# USB_9.net
KiCad netlist of a schematic drawn in Altium Designer
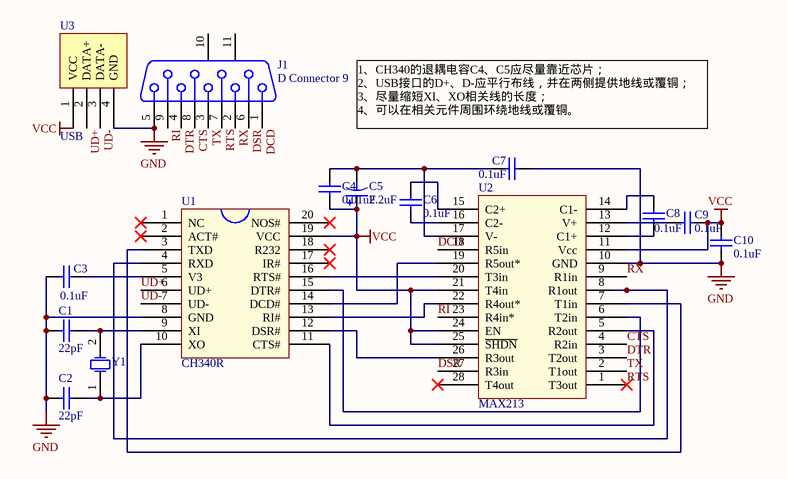
[diagram p0: USB转9线串口.SchDoc]

(export (version "E")
  (design (tool "Eeschema 10.0.6"))
  (components
    (comp (ref "C1")
      (value "22pF")
      (footprint "C1206")
      (description "Capacitor")
      (fields (field (name "PUBLISHER") "Altium Limited"))
      (libsource (lib "Miscellaneous Devices") (part "Cap"))
    )
    (comp (ref "C2")
      (value "22pF")
      (footprint "C1206")
      (description "Capacitor")
      (fields (field (name "PUBLISHER") "Altium Limited"))
      (libsource (lib "Miscellaneous Devices") (part "Cap"))
    )
    (comp (ref "C3")
      (value "0.1uF")
      (footprint "C1206")
      (description "Capacitor")
      (fields (field (name "PUBLISHER") "Altium Limited"))
      (libsource (lib "Miscellaneous Devices") (part "Cap"))
    )
    (comp (ref "C4")
      (value "0.01uF")
      (footprint "C1206")
      (description "Capacitor")
      (fields (field (name "PUBLISHER") "Altium Limited"))
      (libsource (lib "Miscellaneous Devices") (part "Cap"))
    )
    (comp (ref "C5")
      (value "2.2uF")
      (footprint "C1206")
      (description "Polarized Capacitor (Radial)")
      (fields (field (name "Comment") "Cap Pol1") (field (name "PUBLISHER") "Altium Limited"))
      (libsource (lib "Miscellaneous Devices") (part "Cap Pol1"))
    )
    (comp (ref "C6")
      (value "0.1uF")
      (footprint "C1206")
      (description "Capacitor")
      (fields (field (name "PUBLISHER") "Altium Limited"))
      (libsource (lib "Miscellaneous Devices") (part "Cap"))
    )
    (comp (ref "C7")
      (value "0.1uF")
      (footprint "C1206")
      (description "Capacitor")
      (fields (field (name "PUBLISHER") "Altium Limited"))
      (libsource (lib "Miscellaneous Devices") (part "Cap"))
    )
    (comp (ref "C8")
      (value "0.1uF")
      (footprint "C1206")
      (description "Capacitor")
      (fields (field (name "PUBLISHER") "Altium Limited"))
      (libsource (lib "Miscellaneous Devices") (part "Cap"))
    )
    (comp (ref "C9")
      (value "0.1uF")
      (footprint "C1206")
      (description "Capacitor")
      (fields (field (name "PUBLISHER") "Altium Limited"))
      (libsource (lib "Miscellaneous Devices") (part "Cap"))
    )
    (comp (ref "C10")
      (value "0.1uF")
      (footprint "C1206")
      (description "Capacitor")
      (fields (field (name "PUBLISHER") "Altium Limited"))
      (libsource (lib "Miscellaneous Devices") (part "Cap"))
    )
    (comp (ref "J1")
      (value "D Connector 9")
      (footprint "DSUB1.385-2H9")
      (description "Receptacle Assembly, 9 Position, Right Angle")
      (fields (field (name "PUBLISHER") "Altium Limited"))
      (libsource (lib "自定义库") (part "D Connector 9"))
    )
    (comp (ref "U1") (value "CH340R") (footprint "SSOP-20") (libsource (lib "自定义库") (part "CH340R")))
    (comp (ref "U2") (value "MAX213") (footprint "SSOP-28") (libsource (lib "自定义库") (part "MAX213")))
    (comp (ref "U3") (value "USB") (footprint "USB-A") (libsource (lib "自定义库") (part "USB")))
    (comp (ref "Y1")
      (value "XTAL")
      (footprint "R38")
      (description "Crystal Oscillator")
      (fields (field (name "PUBLISHER") "Altium Limited"))
      (libsource (lib "自定义库") (part "XTAL"))
    )
  )
  (nets
    (net (code "1") (name "/CTS") (class "Default")
      (node (ref "J1") (pin "8") (pinfunction "8_8") (pintype "passive"))
      (node (ref "U2") (pin "4") (pinfunction "R2in_4") (pintype "passive"))
    )
    (net (code "2") (name "/DCD") (class "Default")
      (node (ref "J1") (pin "1") (pinfunction "1_1") (pintype "passive"))
      (node (ref "U2") (pin "18") (pinfunction "R5in_18") (pintype "passive"))
    )
    (net (code "3") (name "/DSR") (class "Default")
      (node (ref "J1") (pin "6") (pinfunction "6_6") (pintype "passive"))
      (node (ref "U2") (pin "27") (pinfunction "R3in_27") (pintype "passive"))
    )
    (net (code "4") (name "/DTR") (class "Default")
      (node (ref "J1") (pin "4") (pinfunction "4_4") (pintype "passive"))
      (node (ref "U2") (pin "3") (pinfunction "T2out_3") (pintype "passive"))
    )
    (net (code "5") (name "/RI") (class "Default")
      (node (ref "J1") (pin "9") (pinfunction "9_9") (pintype "passive"))
      (node (ref "U2") (pin "23") (pinfunction "R4in*_23") (pintype "passive"))
    )
    (net (code "6") (name "/RTS") (class "Default")
      (node (ref "J1") (pin "7") (pinfunction "7_7") (pintype "passive"))
      (node (ref "U2") (pin "1") (pinfunction "T3out_1") (pintype "passive"))
    )
    (net (code "7") (name "/RX") (class "Default")
      (node (ref "J1") (pin "2") (pinfunction "2_2") (pintype "passive"))
      (node (ref "U2") (pin "9") (pinfunction "R1in_9") (pintype "passive"))
    )
    (net (code "8") (name "/TX") (class "Default")
      (node (ref "J1") (pin "3") (pinfunction "3_3") (pintype "passive"))
      (node (ref "U2") (pin "2") (pinfunction "T1out_2") (pintype "passive"))
    )
    (net (code "9") (name "/UD+") (class "Default")
      (node (ref "U1") (pin "6") (pinfunction "UD+_6") (pintype "passive"))
      (node (ref "U3") (pin "2") (pinfunction "DATA+_2") (pintype "passive"))
    )
    (net (code "10") (name "/UD-") (class "Default")
      (node (ref "U1") (pin "7") (pinfunction "UD-_7") (pintype "passive"))
      (node (ref "U3") (pin "3") (pinfunction "DATA-_3") (pintype "passive"))
    )
    (net (code "11") (name "GND") (class "Default")
      (node (ref "C1") (pin "2") (pinfunction "2_2") (pintype "passive"))
      (node (ref "C10") (pin "1") (pinfunction "1_1") (pintype "passive"))
      (node (ref "C2") (pin "2") (pinfunction "2_2") (pintype "passive"))
      (node (ref "C3") (pin "1") (pinfunction "1_1") (pintype "passive"))
      (node (ref "C7") (pin "2") (pinfunction "2_2") (pintype "passive"))
      (node (ref "J1") (pin "5") (pinfunction "5_5") (pintype "passive"))
      (node (ref "U1") (pin "8") (pinfunction "GND_8") (pintype "passive"))
      (node (ref "U2") (pin "10") (pinfunction "GND_10") (pintype "passive"))
      (node (ref "U3") (pin "4") (pinfunction "GND_4") (pintype "passive"))
    )
    (net (code "12") (name "Net-(U1-CTS#)") (class "Default")
      (node (ref "U1") (pin "11") (pinfunction "CTS#_11") (pintype "passive"))
      (node (ref "U2") (pin "5") (pinfunction "R2out_5") (pintype "passive"))
    )
    (net (code "13") (name "Net-(U1-DCD#)") (class "Default")
      (node (ref "U1") (pin "14") (pinfunction "DCD#_14") (pintype "passive"))
      (node (ref "U2") (pin "19") (pinfunction "R5out*_19") (pintype "passive"))
    )
    (net (code "14") (name "Net-(U1-DSR#)") (class "Default")
      (node (ref "U1") (pin "12") (pinfunction "DSR#_12") (pintype "passive"))
      (node (ref "U2") (pin "26") (pinfunction "R3out_26") (pintype "passive"))
    )
    (net (code "15") (name "Net-(U1-DTR#)") (class "Default")
      (node (ref "U1") (pin "15") (pinfunction "DTR#_15") (pintype "passive"))
      (node (ref "U2") (pin "6") (pinfunction "T2in_6") (pintype "passive"))
    )
    (net (code "16") (name "Net-(U1-RI#)") (class "Default")
      (node (ref "U1") (pin "13") (pinfunction "RI#_13") (pintype "passive"))
      (node (ref "U2") (pin "22") (pinfunction "R4out*_22") (pintype "passive"))
    )
    (net (code "17") (name "Net-(U1-RTS#)") (class "Default")
      (node (ref "U1") (pin "16") (pinfunction "RTS#_16") (pintype "passive"))
      (node (ref "U2") (pin "20") (pinfunction "T3in_20") (pintype "passive"))
    )
    (net (code "18") (name "Net-(U1-RXD)") (class "Default")
      (node (ref "U1") (pin "4") (pinfunction "RXD_4") (pintype "passive"))
      (node (ref "U2") (pin "8") (pinfunction "R1out_8") (pintype "passive"))
    )
    (net (code "19") (name "Net-(U1-TXD)") (class "Default")
      (node (ref "U1") (pin "3") (pinfunction "TXD_3") (pintype "passive"))
      (node (ref "U2") (pin "7") (pinfunction "T1in_7") (pintype "passive"))
    )
    (net (code "20") (name "Net-(U1-V3)") (class "Default")
      (node (ref "C3") (pin "2") (pinfunction "2_2") (pintype "passive"))
      (node (ref "U1") (pin "5") (pinfunction "V3_5") (pintype "passive"))
    )
    (net (code "21") (name "Net-(U1-XI)") (class "Default")
      (node (ref "C1") (pin "1") (pinfunction "1_1") (pintype "passive"))
      (node (ref "U1") (pin "9") (pinfunction "XI_9") (pintype "passive"))
      (node (ref "Y1") (pin "2") (pinfunction "OSC2_2") (pintype "passive"))
    )
    (net (code "22") (name "Net-(U1-XO)") (class "Default")
      (node (ref "C2") (pin "1") (pinfunction "1_1") (pintype "passive"))
      (node (ref "U1") (pin "10") (pinfunction "XO_10") (pintype "passive"))
      (node (ref "Y1") (pin "1") (pinfunction "OSC1_1") (pintype "passive"))
    )
    (net (code "23") (name "Net-(U2-C1+)") (class "Default")
      (node (ref "C8") (pin "1") (pinfunction "1_1") (pintype "passive"))
      (node (ref "U2") (pin "12") (pinfunction "C1+_12") (pintype "passive"))
    )
    (net (code "24") (name "Net-(U2-C1-)") (class "Default")
      (node (ref "C8") (pin "2") (pinfunction "2_2") (pintype "passive"))
      (node (ref "U2") (pin "14") (pinfunction "C1-_14") (pintype "passive"))
    )
    (net (code "25") (name "Net-(U2-C2+)") (class "Default")
      (node (ref "C6") (pin "2") (pinfunction "2_2") (pintype "passive"))
      (node (ref "U2") (pin "15") (pinfunction "C2+_15") (pintype "passive"))
    )
    (net (code "26") (name "Net-(U2-C2-)") (class "Default")
      (node (ref "C6") (pin "1") (pinfunction "1_1") (pintype "passive"))
      (node (ref "U2") (pin "16") (pinfunction "C2-_16") (pintype "passive"))
    )
    (net (code "27") (name "Net-(U2-V+)") (class "Default")
      (node (ref "C9") (pin "1") (pinfunction "1_1") (pintype "passive"))
      (node (ref "U2") (pin "13") (pinfunction "V+_13") (pintype "passive"))
    )
    (net (code "28") (name "Net-(U2-V-)") (class "Default")
      (node (ref "C4") (pin "2") (pinfunction "2_2") (pintype "passive"))
      (node (ref "C5") (pin "2") (pinfunction "2_2") (pintype "passive"))
      (node (ref "C7") (pin "1") (pinfunction "1_1") (pintype "passive"))
      (node (ref "U2") (pin "17") (pinfunction "V-_17") (pintype "passive"))
    )
    (net (code "29") (name "VCC") (class "Default")
      (node (ref "C10") (pin "2") (pinfunction "2_2") (pintype "passive"))
      (node (ref "C4") (pin "1") (pinfunction "1_1") (pintype "passive"))
      (node (ref "C5") (pin "1") (pinfunction "1_1") (pintype "passive"))
      (node (ref "C9") (pin "2") (pinfunction "2_2") (pintype "passive"))
      (node (ref "U1") (pin "19") (pinfunction "VCC_19") (pintype "passive"))
      (node (ref "U2") (pin "11") (pinfunction "Vcc_11") (pintype "passive"))
      (node (ref "U2") (pin "21") (pinfunction "T4in_21") (pintype "passive"))
      (node (ref "U2") (pin "24") (pinfunction "EN_24") (pintype "passive"))
      (node (ref "U2") (pin "25") (pinfunction "~{SHDN}_25") (pintype "passive"))
      (node (ref "U3") (pin "1") (pinfunction "VCC_1") (pintype "passive"))
    )
    (net (code "30") (name "unconnected-(J1-MH1-Pad10)") (class "Default")
      (node (ref "J1") (pin "10") (pinfunction "MH1_10") (pintype "passive"))
    )
    (net (code "31") (name "unconnected-(J1-MH2-Pad11)") (class "Default")
      (node (ref "J1") (pin "11") (pinfunction "MH2_11") (pintype "passive"))
    )
    (net (code "32") (name "unconnected-(U1-ACT#-Pad2)") (class "Default")
      (node (ref "U1") (pin "2") (pinfunction "ACT#_2") (pintype "passive+no_connect"))
    )
    (net (code "33") (name "unconnected-(U1-IR#-Pad17)") (class "Default")
      (node (ref "U1") (pin "17") (pinfunction "IR#_17") (pintype "passive+no_connect"))
    )
    (net (code "34") (name "unconnected-(U1-NC-Pad1)") (class "Default")
      (node (ref "U1") (pin "1") (pinfunction "NC_1") (pintype "passive+no_connect"))
    )
    (net (code "35") (name "unconnected-(U1-NOS#-Pad20)") (class "Default")
      (node (ref "U1") (pin "20") (pinfunction "NOS#_20") (pintype "passive+no_connect"))
    )
    (net (code "36") (name "unconnected-(U1-R232-Pad18)") (class "Default")
      (node (ref "U1") (pin "18") (pinfunction "R232_18") (pintype "passive+no_connect"))
    )
    (net (code "37") (name "unconnected-(U2-T4out-Pad28)") (class "Default")
      (node (ref "U2") (pin "28") (pinfunction "T4out_28") (pintype "passive+no_connect"))
    )
    (net (code "38") (name "unconnected-(U3-NC-Pad5)") (class "Default")
      (node (ref "U3") (pin "5") (pinfunction "NC_5") (pintype "passive"))
    )
    (net (code "39") (name "unconnected-(U3-NC-Pad6)") (class "Default")
      (node (ref "U3") (pin "6") (pinfunction "NC_6") (pintype "passive"))
    )
  )
)
